# Half_Slave.net
KiCad netlist of a schematic drawn in Altium Designer
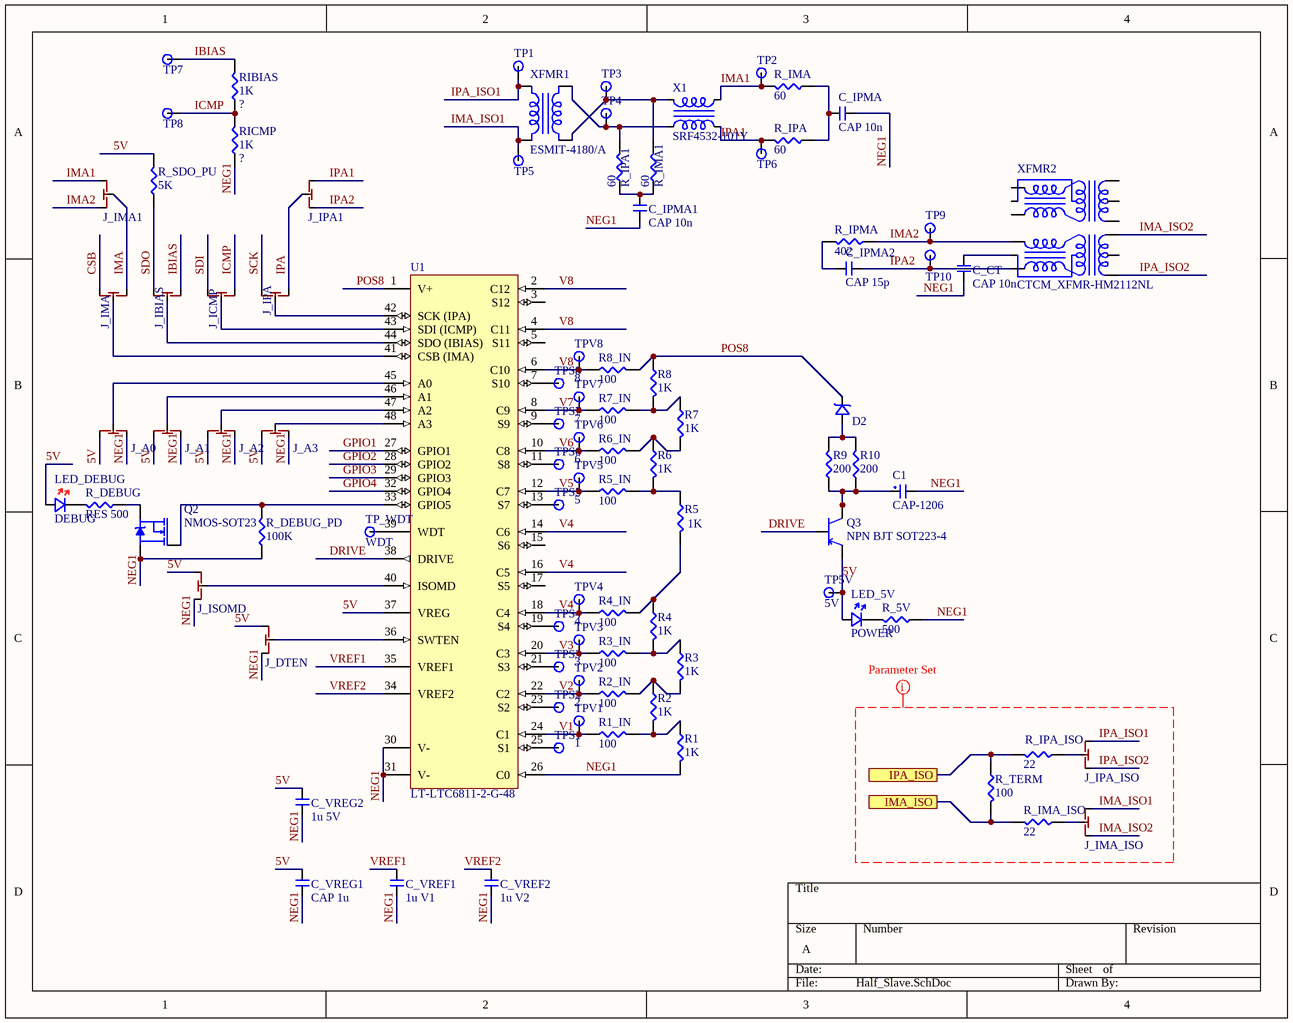
[diagram p0: Half_Slave.SchDoc]

(export (version "E")
  (design (tool "Eeschema 10.0.6"))
  (components
    (comp (ref "C1")
      (value "CAP-1206")
      (footprint "CAPCP3216X16N")
      (libsource (lib "LTC6811") (part "CAP-1206"))
    )
    (comp (ref "C_CT")
      (value "CAP 10n")
      (footprint "CAP-0603")
      (description "CAP-0603")
      (libsource (lib "ife18_TS_BMS_LTC6813_v2_Library") (part "CAP-0603"))
    )
    (comp (ref "C_IPMA")
      (value "CAP 10n")
      (footprint "CAP-0603")
      (description "CAP-0603")
      (libsource (lib "ife18_TS_BMS_LTC6813_v2_Library") (part "CAP-0603"))
    )
    (comp (ref "C_IPMA1")
      (value "CAP 10n")
      (footprint "CAP-0603")
      (description "CAP-0603")
      (libsource (lib "ife18_TS_BMS_LTC6813_v2_Library") (part "CAP-0603"))
    )
    (comp (ref "C_IPMA2")
      (value "CAP 15p")
      (footprint "CAP-0603")
      (description "CAP-0603")
      (libsource (lib "ife18_TS_BMS_LTC6813_v2_Library") (part "CAP-0603"))
    )
    (comp (ref "C_VREF1")
      (value "1u V1")
      (footprint "CAP-0603")
      (description "CAP-0603")
      (libsource (lib "altium-import") (part "root_1_CAP-0603_"))
    )
    (comp (ref "C_VREF2")
      (value "1u V2")
      (footprint "CAP-0603")
      (description "CAP-0603")
      (libsource (lib "altium-import") (part "root_1_CAP-0603_"))
    )
    (comp (ref "C_VREG1")
      (value "CAP 1u")
      (footprint "CAP-0603")
      (description "CAP-0603")
      (libsource (lib "altium-import") (part "root_1_CAP-0603_"))
    )
    (comp (ref "C_VREG2")
      (value "1u 5V")
      (footprint "CAP-0603")
      (description "CAP-0603")
      (libsource (lib "altium-import") (part "root_1_CAP-0603_"))
    )
    (comp (ref "D2") (value "?") (footprint "SMB") (libsource (lib "ife19_Elec_Library") (part "DIODE-SMB")))
    (comp (ref "J_A0")
      (value "DPDT Solder Jumper")
      (footprint "DPDT Solder")
      (libsource (lib "LTC6811") (part "DPDT Solder"))
    )
    (comp (ref "J_A1")
      (value "DPDT Solder Jumper")
      (footprint "DPDT Solder")
      (libsource (lib "LTC6811") (part "DPDT Solder"))
    )
    (comp (ref "J_A2")
      (value "DPDT Solder Jumper")
      (footprint "DPDT Solder")
      (libsource (lib "LTC6811") (part "DPDT Solder"))
    )
    (comp (ref "J_A3")
      (value "DPDT Solder Jumper")
      (footprint "DPDT Solder")
      (libsource (lib "LTC6811") (part "DPDT Solder"))
    )
    (comp (ref "J_DTEN")
      (value "DPDT Solder Jumper")
      (footprint "DPDT Solder")
      (libsource (lib "LTC6811") (part "DPDT Solder"))
    )
    (comp (ref "J_IBIAS")
      (value "DPDT Solder Jumper")
      (footprint "DPDT Solder")
      (libsource (lib "LTC6811") (part "DPDT Solder"))
    )
    (comp (ref "J_ICMP")
      (value "DPDT Solder Jumper")
      (footprint "DPDT Solder")
      (libsource (lib "LTC6811") (part "DPDT Solder"))
    )
    (comp (ref "J_IMA")
      (value "DPDT Solder Jumper")
      (footprint "DPDT Solder")
      (libsource (lib "LTC6811") (part "DPDT Solder"))
    )
    (comp (ref "J_IMA1")
      (value "DPDT Solder Jumper")
      (footprint "DPDT Solder")
      (libsource (lib "LTC6811") (part "DPDT Solder"))
    )
    (comp (ref "J_IMA_ISO")
      (value "DPDT Solder Jumper")
      (footprint "DPDT Solder")
      (libsource (lib "LTC6811") (part "DPDT Solder"))
    )
    (comp (ref "J_IPA")
      (value "DPDT Solder Jumper")
      (footprint "DPDT Solder")
      (libsource (lib "LTC6811") (part "DPDT Solder"))
    )
    (comp (ref "J_IPA1")
      (value "DPDT Solder Jumper")
      (footprint "DPDT Solder")
      (libsource (lib "LTC6811") (part "DPDT Solder"))
    )
    (comp (ref "J_IPA_ISO")
      (value "DPDT Solder Jumper")
      (footprint "DPDT Solder")
      (libsource (lib "LTC6811") (part "DPDT Solder"))
    )
    (comp (ref "J_ISOMD")
      (value "DPDT Solder Jumper")
      (footprint "DPDT Solder")
      (libsource (lib "LTC6811") (part "DPDT Solder"))
    )
    (comp (ref "LED_5V")
      (value "POWER")
      (footprint "LEDBLUE-0603")
      (libsource (lib "ife19_Elec_Library") (part "LEDBLUE-0603"))
    )
    (comp (ref "LED_DEBUG")
      (value "DEBUG")
      (footprint "LEDRED-0603")
      (libsource (lib "ife19_Elec_Library") (part "LEDRED-0603"))
    )
    (comp (ref "Q2")
      (value "NMOS-SOT23")
      (footprint "SOT23")
      (libsource (lib "ife19_Elec_Library") (part "NMOS-SOT23"))
    )
    (comp (ref "Q3")
      (value "NPN BJT SOT223-4")
      (footprint "SOT223")
      (description "BCP54,115")
      (libsource (lib "ife19_Elec_Library") (part "NPN_SOT223-4"))
    )
    (comp (ref "R1")
      (value "1K")
      (footprint "RES-0603")
      (libsource (lib "ife18_TS_BMS_LTC6813_v2_Library") (part "RES-0603"))
    )
    (comp (ref "R1_IN")
      (value "100")
      (footprint "RES-0603")
      (libsource (lib "ife18_TS_BMS_LTC6813_v2_Library") (part "RES-0603"))
    )
    (comp (ref "R2")
      (value "1K")
      (footprint "RES-0603")
      (libsource (lib "ife18_TS_BMS_LTC6813_v2_Library") (part "RES-0603"))
    )
    (comp (ref "R2_IN")
      (value "100")
      (footprint "RES-0603")
      (libsource (lib "ife18_TS_BMS_LTC6813_v2_Library") (part "RES-0603"))
    )
    (comp (ref "R3")
      (value "1K")
      (footprint "RES-0603")
      (libsource (lib "ife18_TS_BMS_LTC6813_v2_Library") (part "RES-0603"))
    )
    (comp (ref "R3_IN")
      (value "100")
      (footprint "RES-0603")
      (libsource (lib "ife18_TS_BMS_LTC6813_v2_Library") (part "RES-0603"))
    )
    (comp (ref "R4")
      (value "1K")
      (footprint "RES-0603")
      (libsource (lib "ife18_TS_BMS_LTC6813_v2_Library") (part "RES-0603"))
    )
    (comp (ref "R4_IN")
      (value "100")
      (footprint "RES-0603")
      (libsource (lib "ife18_TS_BMS_LTC6813_v2_Library") (part "RES-0603"))
    )
    (comp (ref "R5")
      (value "1K")
      (footprint "RES-0603")
      (libsource (lib "ife18_TS_BMS_LTC6813_v2_Library") (part "RES-0603"))
    )
    (comp (ref "R5_IN")
      (value "100")
      (footprint "RES-0603")
      (libsource (lib "ife18_TS_BMS_LTC6813_v2_Library") (part "RES-0603"))
    )
    (comp (ref "R6")
      (value "1K")
      (footprint "RES-0603")
      (libsource (lib "ife18_TS_BMS_LTC6813_v2_Library") (part "RES-0603"))
    )
    (comp (ref "R6_IN")
      (value "100")
      (footprint "RES-0603")
      (libsource (lib "ife18_TS_BMS_LTC6813_v2_Library") (part "RES-0603"))
    )
    (comp (ref "R7")
      (value "1K")
      (footprint "RES-0603")
      (libsource (lib "ife18_TS_BMS_LTC6813_v2_Library") (part "RES-0603"))
    )
    (comp (ref "R7_IN")
      (value "100")
      (footprint "RES-0603")
      (libsource (lib "ife18_TS_BMS_LTC6813_v2_Library") (part "RES-0603"))
    )
    (comp (ref "R8")
      (value "1K")
      (footprint "RES-0603")
      (libsource (lib "ife18_TS_BMS_LTC6813_v2_Library") (part "RES-0603"))
    )
    (comp (ref "R8_IN")
      (value "100")
      (footprint "RES-0603")
      (libsource (lib "ife18_TS_BMS_LTC6813_v2_Library") (part "RES-0603"))
    )
    (comp (ref "R9")
      (value "200")
      (footprint "RES-0603")
      (libsource (lib "ife18_TS_BMS_LTC6813_v2_Library") (part "RES-0603"))
    )
    (comp (ref "R10")
      (value "200")
      (footprint "RES-0603")
      (libsource (lib "ife18_TS_BMS_LTC6813_v2_Library") (part "RES-0603"))
    )
    (comp (ref "RIBIAS")
      (value "1K")
      (footprint "RES-0603")
      (description "RES SMD 0603")
      (fields (field (name "PART") "RES_0603") (field (name "ALTIUM_VALUE") "?"))
      (libsource (lib "IFE") (part "RES"))
    )
    (comp (ref "RICMP")
      (value "1K")
      (footprint "RES-0603")
      (description "RES SMD 0603")
      (fields (field (name "PART") "RES_0603") (field (name "ALTIUM_VALUE") "?"))
      (libsource (lib "IFE") (part "RES"))
    )
    (comp (ref "R_5V")
      (value "500")
      (footprint "RES-0603")
      (libsource (lib "altium-import") (part "root_2_RES-0603_"))
    )
    (comp (ref "R_DEBUG")
      (value "RES 500")
      (footprint "RES-0603")
      (libsource (lib "altium-import") (part "root_2_RES-0603_"))
    )
    (comp (ref "R_DEBUG_PD")
      (value "100K")
      (footprint "RES-0603")
      (libsource (lib "ife18_TS_BMS_LTC6813_v2_Library") (part "RES-0603"))
    )
    (comp (ref "R_IMA")
      (value "60")
      (footprint "RES-0603")
      (libsource (lib "ife18_TS_BMS_LTC6813_v2_Library") (part "RES-0603"))
    )
    (comp (ref "R_IMA1")
      (value "60")
      (footprint "RES-0603")
      (libsource (lib "ife18_TS_BMS_LTC6813_v2_Library") (part "RES-0603"))
    )
    (comp (ref "R_IMA_ISO")
      (value "22")
      (footprint "RES-0603")
      (libsource (lib "ife18_TS_BMS_LTC6813_v2_Library") (part "RES-0603"))
    )
    (comp (ref "R_IPA")
      (value "60")
      (footprint "RES-0603")
      (libsource (lib "ife18_TS_BMS_LTC6813_v2_Library") (part "RES-0603"))
    )
    (comp (ref "R_IPA1")
      (value "60")
      (footprint "RES-0603")
      (libsource (lib "ife18_TS_BMS_LTC6813_v2_Library") (part "RES-0603"))
    )
    (comp (ref "R_IPA_ISO")
      (value "22")
      (footprint "RES-0603")
      (libsource (lib "ife18_TS_BMS_LTC6813_v2_Library") (part "RES-0603"))
    )
    (comp (ref "R_IPMA")
      (value "402")
      (footprint "RES-0603")
      (libsource (lib "ife18_TS_BMS_LTC6813_v2_Library") (part "RES-0603"))
    )
    (comp (ref "R_SDO_PU")
      (value "5K")
      (footprint "RES-0603")
      (libsource (lib "ife18_TS_BMS_LTC6813_v2_Library") (part "RES-0603"))
    )
    (comp (ref "R_TERM")
      (value "100")
      (footprint "RES-0603")
      (libsource (lib "ife18_TS_BMS_LTC6813_v2_Library") (part "RES-0603"))
    )
    (comp (ref "TP1")
      (value "IP_ISO")
      (footprint "Testpoint")
      (libsource (lib "ife19_Elec_Library") (part "Testpoint"))
    )
    (comp (ref "TP2")
      (value "IMA")
      (footprint "Testpoint")
      (libsource (lib "ife19_Elec_Library") (part "Testpoint"))
    )
    (comp (ref "TP3")
      (value "IM_F")
      (footprint "Testpoint")
      (libsource (lib "ife19_Elec_Library") (part "Testpoint"))
    )
    (comp (ref "TP4")
      (value "IP_F")
      (footprint "Testpoint")
      (libsource (lib "ife19_Elec_Library") (part "Testpoint"))
    )
    (comp (ref "TP5")
      (value "IM_ISO")
      (footprint "Testpoint")
      (libsource (lib "ife19_Elec_Library") (part "Testpoint"))
    )
    (comp (ref "TP5V")
      (value "5V")
      (footprint "Testpoint")
      (libsource (lib "ife19_Elec_Library") (part "Testpoint"))
    )
    (comp (ref "TP6")
      (value "IPA")
      (footprint "Testpoint")
      (libsource (lib "ife19_Elec_Library") (part "Testpoint"))
    )
    (comp (ref "TP7")
      (value "IBIAS")
      (footprint "Testpoint")
      (libsource (lib "ife19_Elec_Library") (part "Testpoint"))
    )
    (comp (ref "TP8")
      (value "ICMP")
      (footprint "Testpoint")
      (libsource (lib "ife19_Elec_Library") (part "Testpoint"))
    )
    (comp (ref "TP9")
      (value "IMA")
      (footprint "Testpoint")
      (libsource (lib "ife19_Elec_Library") (part "Testpoint"))
    )
    (comp (ref "TP10")
      (value "IPA")
      (footprint "Testpoint")
      (libsource (lib "ife19_Elec_Library") (part "Testpoint"))
    )
    (comp (ref "TPS1")
      (value "~")
      (footprint "Testpoint")
      (libsource (lib "ife19_Elec_Library") (part "Testpoint"))
    )
    (comp (ref "TPS2")
      (value "~")
      (footprint "Testpoint")
      (libsource (lib "ife19_Elec_Library") (part "Testpoint"))
    )
    (comp (ref "TPS3")
      (value "~")
      (footprint "Testpoint")
      (libsource (lib "ife19_Elec_Library") (part "Testpoint"))
    )
    (comp (ref "TPS4")
      (value "~")
      (footprint "Testpoint")
      (libsource (lib "ife19_Elec_Library") (part "Testpoint"))
    )
    (comp (ref "TPS5")
      (value "~")
      (footprint "Testpoint")
      (libsource (lib "ife19_Elec_Library") (part "Testpoint"))
    )
    (comp (ref "TPS6")
      (value "~")
      (footprint "Testpoint")
      (libsource (lib "ife19_Elec_Library") (part "Testpoint"))
    )
    (comp (ref "TPS7")
      (value "~")
      (footprint "Testpoint")
      (libsource (lib "ife19_Elec_Library") (part "Testpoint"))
    )
    (comp (ref "TPS8")
      (value "~")
      (footprint "Testpoint")
      (libsource (lib "ife19_Elec_Library") (part "Testpoint"))
    )
    (comp (ref "TPV1")
      (value "1")
      (footprint "Testpoint")
      (libsource (lib "ife19_Elec_Library") (part "Testpoint"))
    )
    (comp (ref "TPV2")
      (value "2")
      (footprint "Testpoint")
      (libsource (lib "ife19_Elec_Library") (part "Testpoint"))
    )
    (comp (ref "TPV3")
      (value "3")
      (footprint "Testpoint")
      (libsource (lib "ife19_Elec_Library") (part "Testpoint"))
    )
    (comp (ref "TPV4")
      (value "4")
      (footprint "Testpoint")
      (libsource (lib "ife19_Elec_Library") (part "Testpoint"))
    )
    (comp (ref "TPV5")
      (value "5")
      (footprint "Testpoint")
      (libsource (lib "ife19_Elec_Library") (part "Testpoint"))
    )
    (comp (ref "TPV6")
      (value "6")
      (footprint "Testpoint")
      (libsource (lib "ife19_Elec_Library") (part "Testpoint"))
    )
    (comp (ref "TPV7")
      (value "7")
      (footprint "Testpoint")
      (libsource (lib "ife19_Elec_Library") (part "Testpoint"))
    )
    (comp (ref "TPV8")
      (value "8")
      (footprint "Testpoint")
      (libsource (lib "ife19_Elec_Library") (part "Testpoint"))
    )
    (comp (ref "TP_WDT")
      (value "WDT")
      (footprint "Testpoint")
      (libsource (lib "ife19_Elec_Library") (part "Testpoint"))
    )
    (comp (ref "U1")
      (value "LT-LTC6811-2-G-48")
      (footprint "SSOP-48N")
      (libsource (lib "LTC6811") (part "LT-LTC6811-2-G-48"))
    )
    (comp (ref "X1")
      (value "SRF4532-101Y")
      (footprint "SRF4532")
      (libsource (lib "ife19_Elec_Library") (part "CMC_SRF4532"))
    )
    (comp (ref "XFMR1")
      (value "ESMIT-4180/A")
      (footprint "ISOXFMR_ESMIT4180")
      (libsource (lib "ife19_Elec_Library") (part "ISOXFMR_ESMIT4180"))
    )
    (comp (ref "XFMR2")
      (value "CTCM_XFMR-HM2112NL")
      (footprint "HM2112NL")
      (libsource (lib "ife19_Elec_Library") (part "CTCM_XFMR-HM2112NL"))
    )
  )
  (nets
    (net (code "1") (name "/5V") (class "Default")
      (node (ref "C_VREG1") (pin "2") (pinfunction "2_2") (pintype "passive"))
      (node (ref "C_VREG2") (pin "2") (pinfunction "2_2") (pintype "passive"))
      (node (ref "J_A0") (pin "2") (pintype "passive"))
      (node (ref "J_A1") (pin "2") (pintype "passive"))
      (node (ref "J_A2") (pin "2") (pintype "passive"))
      (node (ref "J_A3") (pin "2") (pintype "passive"))
      (node (ref "J_DTEN") (pin "2") (pintype "passive"))
      (node (ref "J_ISOMD") (pin "2") (pintype "passive"))
      (node (ref "LED_5V") (pin "A") (pinfunction "A_A") (pintype "passive"))
      (node (ref "LED_DEBUG") (pin "A") (pinfunction "A_A") (pintype "passive"))
      (node (ref "Q3") (pin "3") (pinfunction "E_3") (pintype "passive"))
      (node (ref "R_SDO_PU") (pin "2") (pinfunction "2_2") (pintype "passive"))
      (node (ref "TP5V") (pin "1") (pinfunction "1_1") (pintype "passive"))
      (node (ref "U1") (pin "37") (pinfunction "VREG_37") (pintype "power_in"))
    )
    (net (code "2") (name "/CSB") (class "Default") (node (ref "J_IMA") (pin "1") (pintype "passive")))
    (net (code "3") (name "/DRIVE") (class "Default")
      (node (ref "Q3") (pin "1") (pinfunction "B_1") (pintype "passive"))
      (node (ref "U1") (pin "38") (pinfunction "DRIVE_38") (pintype "output"))
    )
    (net (code "4") (name "/GPIO1") (class "Default")
      (node (ref "U1") (pin "27") (pinfunction "GPIO1_27") (pintype "bidirectional"))
    )
    (net (code "5") (name "/GPIO2") (class "Default")
      (node (ref "U1") (pin "28") (pinfunction "GPIO2_28") (pintype "bidirectional"))
    )
    (net (code "6") (name "/GPIO3") (class "Default")
      (node (ref "U1") (pin "29") (pinfunction "GPIO3_29") (pintype "bidirectional"))
    )
    (net (code "7") (name "/GPIO4") (class "Default")
      (node (ref "U1") (pin "32") (pinfunction "GPIO4_32") (pintype "bidirectional"))
    )
    (net (code "8") (name "/IBIAS") (class "Default")
      (node (ref "J_IBIAS") (pin "2") (pintype "passive"))
      (node (ref "RIBIAS") (pin "2") (pinfunction "2_2") (pintype "passive"))
      (node (ref "TP7") (pin "1") (pinfunction "1_1") (pintype "passive"))
    )
    (net (code "9") (name "/ICMP") (class "Default")
      (node (ref "J_ICMP") (pin "2") (pintype "passive"))
      (node (ref "RIBIAS") (pin "1") (pinfunction "1_1") (pintype "passive"))
      (node (ref "RICMP") (pin "2") (pinfunction "2_2") (pintype "passive"))
      (node (ref "TP8") (pin "1") (pinfunction "1_1") (pintype "passive"))
    )
    (net (code "10") (name "/IMA") (class "Default")
      (node (ref "J_IMA") (pin "2") (pintype "passive"))
      (node (ref "J_IMA1") (pin "3") (pintype "passive"))
    )
    (net (code "11") (name "/IMA1") (class "Default")
      (node (ref "J_IMA1") (pin "2") (pintype "passive"))
      (node (ref "R_IMA") (pin "2") (pinfunction "2_2") (pintype "passive"))
      (node (ref "TP2") (pin "1") (pinfunction "1_1") (pintype "passive"))
      (node (ref "X1") (pin "1") (pinfunction "1_1") (pintype "passive"))
    )
    (net (code "12") (name "/IMA2") (class "Default")
      (node (ref "J_IMA1") (pin "1") (pintype "passive"))
      (node (ref "R_IPMA") (pin "1") (pinfunction "1_1") (pintype "passive"))
      (node (ref "TP9") (pin "1") (pinfunction "1_1") (pintype "passive"))
      (node (ref "XFMR2") (pin "9") (pinfunction "9_9") (pintype "passive"))
    )
    (net (code "13") (name "/IMA_ISO") (class "Default")
      (node (ref "R_IMA_ISO") (pin "2") (pinfunction "2_2") (pintype "passive"))
      (node (ref "R_TERM") (pin "2") (pinfunction "2_2") (pintype "passive"))
    )
    (net (code "14") (name "/IMA_ISO1") (class "Default")
      (node (ref "J_IMA_ISO") (pin "2") (pintype "passive"))
      (node (ref "TP5") (pin "1") (pinfunction "1_1") (pintype "passive"))
      (node (ref "XFMR1") (pin "1") (pinfunction "1_1") (pintype "passive"))
    )
    (net (code "15") (name "/IMA_ISO2") (class "Default")
      (node (ref "J_IMA_ISO") (pin "1") (pintype "passive"))
      (node (ref "XFMR2") (pin "4") (pinfunction "4_4") (pintype "passive"))
    )
    (net (code "16") (name "/IPA") (class "Default")
      (node (ref "J_IPA") (pin "2") (pintype "passive"))
      (node (ref "J_IPA1") (pin "3") (pintype "passive"))
    )
    (net (code "17") (name "/IPA1") (class "Default")
      (node (ref "J_IPA1") (pin "2") (pintype "passive"))
      (node (ref "R_IPA") (pin "2") (pinfunction "2_2") (pintype "passive"))
      (node (ref "TP6") (pin "1") (pinfunction "1_1") (pintype "passive"))
      (node (ref "X1") (pin "4") (pinfunction "4_4") (pintype "passive"))
    )
    (net (code "18") (name "/IPA2") (class "Default")
      (node (ref "C_IPMA2") (pin "1") (pinfunction "1_1") (pintype "passive"))
      (node (ref "J_IPA1") (pin "1") (pintype "passive"))
      (node (ref "TP10") (pin "1") (pinfunction "1_1") (pintype "passive"))
      (node (ref "XFMR2") (pin "7") (pinfunction "7_7") (pintype "passive"))
    )
    (net (code "19") (name "/IPA_ISO") (class "Default")
      (node (ref "R_IPA_ISO") (pin "2") (pinfunction "2_2") (pintype "passive"))
      (node (ref "R_TERM") (pin "1") (pinfunction "1_1") (pintype "passive"))
    )
    (net (code "20") (name "/IPA_ISO1") (class "Default")
      (node (ref "J_IPA_ISO") (pin "2") (pintype "passive"))
      (node (ref "TP1") (pin "1") (pinfunction "1_1") (pintype "passive"))
      (node (ref "XFMR1") (pin "2") (pinfunction "2_2") (pintype "passive"))
    )
    (net (code "21") (name "/IPA_ISO2") (class "Default")
      (node (ref "J_IPA_ISO") (pin "1") (pintype "passive"))
      (node (ref "XFMR2") (pin "6") (pinfunction "6_6") (pintype "passive"))
    )
    (net (code "22") (name "/NEG1") (class "Default")
      (node (ref "C1") (pin "2") (pinfunction "2_2") (pintype "passive"))
      (node (ref "C_CT") (pin "2") (pinfunction "2_2") (pintype "passive"))
      (node (ref "C_IPMA") (pin "1") (pinfunction "1_1") (pintype "passive"))
      (node (ref "C_IPMA1") (pin "1") (pinfunction "1_1") (pintype "passive"))
      (node (ref "C_VREF1") (pin "1") (pinfunction "1_1") (pintype "passive"))
      (node (ref "C_VREF2") (pin "1") (pinfunction "1_1") (pintype "passive"))
      (node (ref "C_VREG1") (pin "1") (pinfunction "1_1") (pintype "passive"))
      (node (ref "C_VREG2") (pin "1") (pinfunction "1_1") (pintype "passive"))
      (node (ref "J_A0") (pin "1") (pintype "passive"))
      (node (ref "J_A1") (pin "1") (pintype "passive"))
      (node (ref "J_A2") (pin "1") (pintype "passive"))
      (node (ref "J_A3") (pin "1") (pintype "passive"))
      (node (ref "J_DTEN") (pin "1") (pintype "passive"))
      (node (ref "J_ISOMD") (pin "1") (pintype "passive"))
      (node (ref "Q2") (pin "2") (pinfunction "S_2") (pintype "passive"))
      (node (ref "R1") (pin "2") (pinfunction "2_2") (pintype "passive"))
      (node (ref "RICMP") (pin "1") (pinfunction "1_1") (pintype "passive"))
      (node (ref "R_5V") (pin "1") (pinfunction "1_1") (pintype "passive"))
      (node (ref "R_DEBUG_PD") (pin "1") (pinfunction "1_1") (pintype "passive"))
      (node (ref "U1") (pin "26") (pinfunction "C0_26") (pintype "input"))
      (node (ref "U1") (pin "30") (pinfunction "V-_30") (pintype "power_in"))
      (node (ref "U1") (pin "31") (pinfunction "V-_31") (pintype "power_in"))
    )
    (net (code "23") (name "/POS8") (class "Default")
      (node (ref "D2") (pin "K") (pinfunction "K_K") (pintype "passive"))
      (node (ref "R8") (pin "1") (pinfunction "1_1") (pintype "passive"))
      (node (ref "R8_IN") (pin "2") (pinfunction "2_2") (pintype "passive"))
      (node (ref "U1") (pin "1") (pinfunction "V+_1") (pintype "power_in"))
    )
    (net (code "24") (name "/SCK") (class "Default") (node (ref "J_IPA") (pin "1") (pintype "passive")))
    (net (code "25") (name "/SDI") (class "Default") (node (ref "J_ICMP") (pin "1") (pintype "passive")))
    (net (code "26") (name "/SDO") (class "Default")
      (node (ref "J_IBIAS") (pin "1") (pintype "passive"))
      (node (ref "R_SDO_PU") (pin "1") (pinfunction "1_1") (pintype "passive"))
    )
    (net (code "27") (name "/V1") (class "Default")
      (node (ref "R1_IN") (pin "1") (pinfunction "1_1") (pintype "passive"))
      (node (ref "TPV1") (pin "1") (pinfunction "1_1") (pintype "passive"))
      (node (ref "U1") (pin "24") (pinfunction "C1_24") (pintype "input"))
    )
    (net (code "28") (name "/V2") (class "Default")
      (node (ref "R2_IN") (pin "1") (pinfunction "1_1") (pintype "passive"))
      (node (ref "TPV2") (pin "1") (pinfunction "1_1") (pintype "passive"))
      (node (ref "U1") (pin "22") (pinfunction "C2_22") (pintype "input"))
    )
    (net (code "29") (name "/V3") (class "Default")
      (node (ref "R3_IN") (pin "1") (pinfunction "1_1") (pintype "passive"))
      (node (ref "TPV3") (pin "1") (pinfunction "1_1") (pintype "passive"))
      (node (ref "U1") (pin "20") (pinfunction "C3_20") (pintype "input"))
    )
    (net (code "30") (name "/V4") (class "Default")
      (node (ref "R4_IN") (pin "1") (pinfunction "1_1") (pintype "passive"))
      (node (ref "TPV4") (pin "1") (pinfunction "1_1") (pintype "passive"))
      (node (ref "U1") (pin "14") (pinfunction "C6_14") (pintype "input"))
      (node (ref "U1") (pin "16") (pinfunction "C5_16") (pintype "input"))
      (node (ref "U1") (pin "18") (pinfunction "C4_18") (pintype "input"))
    )
    (net (code "31") (name "/V5") (class "Default")
      (node (ref "R5_IN") (pin "1") (pinfunction "1_1") (pintype "passive"))
      (node (ref "TPV5") (pin "1") (pinfunction "1_1") (pintype "passive"))
      (node (ref "U1") (pin "12") (pinfunction "C7_12") (pintype "input"))
    )
    (net (code "32") (name "/V6") (class "Default")
      (node (ref "R6_IN") (pin "1") (pinfunction "1_1") (pintype "passive"))
      (node (ref "TPV6") (pin "1") (pinfunction "1_1") (pintype "passive"))
      (node (ref "U1") (pin "10") (pinfunction "C8_10") (pintype "input"))
    )
    (net (code "33") (name "/V7") (class "Default")
      (node (ref "R7_IN") (pin "1") (pinfunction "1_1") (pintype "passive"))
      (node (ref "TPV7") (pin "1") (pinfunction "1_1") (pintype "passive"))
      (node (ref "U1") (pin "8") (pinfunction "C9_8") (pintype "input"))
    )
    (net (code "34") (name "/V8") (class "Default")
      (node (ref "R8_IN") (pin "1") (pinfunction "1_1") (pintype "passive"))
      (node (ref "TPV8") (pin "1") (pinfunction "1_1") (pintype "passive"))
      (node (ref "U1") (pin "2") (pinfunction "C12_2") (pintype "input"))
      (node (ref "U1") (pin "4") (pinfunction "C11_4") (pintype "input"))
      (node (ref "U1") (pin "6") (pinfunction "C10_6") (pintype "input"))
    )
    (net (code "35") (name "/VREF1") (class "Default")
      (node (ref "C_VREF1") (pin "2") (pinfunction "2_2") (pintype "passive"))
      (node (ref "U1") (pin "35") (pinfunction "VREF1_35") (pintype "passive"))
    )
    (net (code "36") (name "/VREF2") (class "Default")
      (node (ref "C_VREF2") (pin "2") (pinfunction "2_2") (pintype "passive"))
      (node (ref "U1") (pin "34") (pinfunction "VREF2_34") (pintype "passive"))
    )
    (net (code "37") (name "Net-(C1-Pad1)") (class "Default")
      (node (ref "C1") (pin "1") (pinfunction "1_1") (pintype "passive"))
      (node (ref "Q3") (pin "2") (pinfunction "C_2") (pintype "passive"))
      (node (ref "Q3") (pin "4") (pinfunction "C_4") (pintype "passive"))
      (node (ref "R10") (pin "1") (pinfunction "1_1") (pintype "passive"))
      (node (ref "R9") (pin "1") (pinfunction "1_1") (pintype "passive"))
    )
    (net (code "38") (name "Net-(C_CT-Pad1)") (class "Default")
      (node (ref "C_CT") (pin "1") (pinfunction "1_1") (pintype "passive"))
      (node (ref "XFMR2") (pin "8") (pinfunction "8_8") (pintype "passive"))
    )
    (net (code "39") (name "Net-(C_IPMA-Pad2)") (class "Default")
      (node (ref "C_IPMA") (pin "2") (pinfunction "2_2") (pintype "passive"))
      (node (ref "R_IMA") (pin "1") (pinfunction "1_1") (pintype "passive"))
      (node (ref "R_IPA") (pin "1") (pinfunction "1_1") (pintype "passive"))
    )
    (net (code "40") (name "Net-(C_IPMA1-Pad2)") (class "Default")
      (node (ref "C_IPMA1") (pin "2") (pinfunction "2_2") (pintype "passive"))
      (node (ref "R_IMA1") (pin "1") (pinfunction "1_1") (pintype "passive"))
      (node (ref "R_IPA1") (pin "1") (pinfunction "1_1") (pintype "passive"))
    )
    (net (code "41") (name "Net-(C_IPMA2-Pad2)") (class "Default")
      (node (ref "C_IPMA2") (pin "2") (pinfunction "2_2") (pintype "passive"))
      (node (ref "R_IPMA") (pin "2") (pinfunction "2_2") (pintype "passive"))
    )
    (net (code "42") (name "Net-(D2-PadA)") (class "Default")
      (node (ref "D2") (pin "A") (pinfunction "A_A") (pintype "passive"))
      (node (ref "R10") (pin "2") (pinfunction "2_2") (pintype "passive"))
      (node (ref "R9") (pin "2") (pinfunction "2_2") (pintype "passive"))
    )
    (net (code "43") (name "Net-(J_IMA_ISO-Pad3)") (class "Default")
      (node (ref "J_IMA_ISO") (pin "3") (pintype "passive"))
      (node (ref "R_IMA_ISO") (pin "1") (pinfunction "1_1") (pintype "passive"))
    )
    (net (code "44") (name "Net-(J_IPA_ISO-Pad3)") (class "Default")
      (node (ref "J_IPA_ISO") (pin "3") (pintype "passive"))
      (node (ref "R_IPA_ISO") (pin "1") (pinfunction "1_1") (pintype "passive"))
    )
    (net (code "45") (name "Net-(LED_5V-PadK)") (class "Default")
      (node (ref "LED_5V") (pin "K") (pinfunction "K_K") (pintype "passive"))
      (node (ref "R_5V") (pin "2") (pinfunction "2_2") (pintype "passive"))
    )
    (net (code "46") (name "Net-(LED_DEBUG-PadK)") (class "Default")
      (node (ref "LED_DEBUG") (pin "K") (pinfunction "K_K") (pintype "passive"))
      (node (ref "R_DEBUG") (pin "2") (pinfunction "2_2") (pintype "passive"))
    )
    (net (code "47") (name "Net-(Q2-D)") (class "Default")
      (node (ref "Q2") (pin "3") (pinfunction "D_3") (pintype "passive"))
      (node (ref "R_DEBUG") (pin "1") (pinfunction "1_1") (pintype "passive"))
    )
    (net (code "48") (name "Net-(Q2-G)") (class "Default")
      (node (ref "Q2") (pin "1") (pinfunction "G_1") (pintype "passive"))
      (node (ref "R_DEBUG_PD") (pin "2") (pinfunction "2_2") (pintype "passive"))
      (node (ref "U1") (pin "33") (pinfunction "GPIO5_33") (pintype "bidirectional"))
    )
    (net (code "49") (name "Net-(R1-Pad1)") (class "Default")
      (node (ref "R1") (pin "1") (pinfunction "1_1") (pintype "passive"))
      (node (ref "R1_IN") (pin "2") (pinfunction "2_2") (pintype "passive"))
      (node (ref "R2") (pin "2") (pinfunction "2_2") (pintype "passive"))
    )
    (net (code "50") (name "Net-(R2-Pad1)") (class "Default")
      (node (ref "R2") (pin "1") (pinfunction "1_1") (pintype "passive"))
      (node (ref "R2_IN") (pin "2") (pinfunction "2_2") (pintype "passive"))
      (node (ref "R3") (pin "2") (pinfunction "2_2") (pintype "passive"))
    )
    (net (code "51") (name "Net-(R3-Pad1)") (class "Default")
      (node (ref "R3") (pin "1") (pinfunction "1_1") (pintype "passive"))
      (node (ref "R3_IN") (pin "2") (pinfunction "2_2") (pintype "passive"))
      (node (ref "R4") (pin "2") (pinfunction "2_2") (pintype "passive"))
    )
    (net (code "52") (name "Net-(R4-Pad1)") (class "Default")
      (node (ref "R4") (pin "1") (pinfunction "1_1") (pintype "passive"))
      (node (ref "R4_IN") (pin "2") (pinfunction "2_2") (pintype "passive"))
      (node (ref "R5") (pin "2") (pinfunction "2_2") (pintype "passive"))
    )
    (net (code "53") (name "Net-(R5-Pad1)") (class "Default")
      (node (ref "R5") (pin "1") (pinfunction "1_1") (pintype "passive"))
      (node (ref "R5_IN") (pin "2") (pinfunction "2_2") (pintype "passive"))
      (node (ref "R6") (pin "2") (pinfunction "2_2") (pintype "passive"))
    )
    (net (code "54") (name "Net-(R6-Pad1)") (class "Default")
      (node (ref "R6") (pin "1") (pinfunction "1_1") (pintype "passive"))
      (node (ref "R6_IN") (pin "2") (pinfunction "2_2") (pintype "passive"))
      (node (ref "R7") (pin "2") (pinfunction "2_2") (pintype "passive"))
    )
    (net (code "55") (name "Net-(R7-Pad1)") (class "Default")
      (node (ref "R7") (pin "1") (pinfunction "1_1") (pintype "passive"))
      (node (ref "R7_IN") (pin "2") (pinfunction "2_2") (pintype "passive"))
      (node (ref "R8") (pin "2") (pinfunction "2_2") (pintype "passive"))
    )
    (net (code "56") (name "Net-(R_IMA1-Pad2)") (class "Default")
      (node (ref "R_IMA1") (pin "2") (pinfunction "2_2") (pintype "passive"))
      (node (ref "TP3") (pin "1") (pinfunction "1_1") (pintype "passive"))
      (node (ref "X1") (pin "2") (pinfunction "2_2") (pintype "passive"))
      (node (ref "XFMR1") (pin "4") (pinfunction "4_4") (pintype "passive"))
    )
    (net (code "57") (name "Net-(R_IPA1-Pad2)") (class "Default")
      (node (ref "R_IPA1") (pin "2") (pinfunction "2_2") (pintype "passive"))
      (node (ref "TP4") (pin "1") (pinfunction "1_1") (pintype "passive"))
      (node (ref "X1") (pin "3") (pinfunction "3_3") (pintype "passive"))
      (node (ref "XFMR1") (pin "3") (pinfunction "3_3") (pintype "passive"))
    )
    (net (code "58") (name "Net-(U1-A0)") (class "Default")
      (node (ref "J_A0") (pin "3") (pintype "passive"))
      (node (ref "U1") (pin "45") (pinfunction "A0_45") (pintype "input"))
    )
    (net (code "59") (name "Net-(U1-A1)") (class "Default")
      (node (ref "J_A1") (pin "3") (pintype "passive"))
      (node (ref "U1") (pin "46") (pinfunction "A1_46") (pintype "input"))
    )
    (net (code "60") (name "Net-(U1-A2)") (class "Default")
      (node (ref "J_A2") (pin "3") (pintype "passive"))
      (node (ref "U1") (pin "47") (pinfunction "A2_47") (pintype "input"))
    )
    (net (code "61") (name "Net-(U1-A3)") (class "Default")
      (node (ref "J_A3") (pin "3") (pintype "passive"))
      (node (ref "U1") (pin "48") (pinfunction "A3_48") (pintype "input"))
    )
    (net (code "62") (name "Net-(U1-CSB_(IMA))") (class "Default")
      (node (ref "J_IMA") (pin "3") (pintype "passive"))
      (node (ref "U1") (pin "41") (pinfunction "CSB_(IMA)_41") (pintype "bidirectional"))
    )
    (net (code "63") (name "Net-(U1-ISOMD)") (class "Default")
      (node (ref "J_ISOMD") (pin "3") (pintype "passive"))
      (node (ref "U1") (pin "40") (pinfunction "ISOMD_40") (pintype "input"))
    )
    (net (code "64") (name "Net-(U1-S1)") (class "Default")
      (node (ref "TPS1") (pin "1") (pinfunction "1_1") (pintype "passive"))
      (node (ref "U1") (pin "25") (pinfunction "S1_25") (pintype "bidirectional"))
    )
    (net (code "65") (name "Net-(U1-S2)") (class "Default")
      (node (ref "TPS2") (pin "1") (pinfunction "1_1") (pintype "passive"))
      (node (ref "U1") (pin "23") (pinfunction "S2_23") (pintype "bidirectional"))
    )
    (net (code "66") (name "Net-(U1-S3)") (class "Default")
      (node (ref "TPS3") (pin "1") (pinfunction "1_1") (pintype "passive"))
      (node (ref "U1") (pin "21") (pinfunction "S3_21") (pintype "bidirectional"))
    )
    (net (code "67") (name "Net-(U1-S4)") (class "Default")
      (node (ref "TPS4") (pin "1") (pinfunction "1_1") (pintype "passive"))
      (node (ref "U1") (pin "19") (pinfunction "S4_19") (pintype "bidirectional"))
    )
    (net (code "68") (name "Net-(U1-S7)") (class "Default")
      (node (ref "TPS5") (pin "1") (pinfunction "1_1") (pintype "passive"))
      (node (ref "U1") (pin "13") (pinfunction "S7_13") (pintype "bidirectional"))
    )
    (net (code "69") (name "Net-(U1-S8)") (class "Default")
      (node (ref "TPS6") (pin "1") (pinfunction "1_1") (pintype "passive"))
      (node (ref "U1") (pin "11") (pinfunction "S8_11") (pintype "bidirectional"))
    )
    (net (code "70") (name "Net-(U1-S9)") (class "Default")
      (node (ref "TPS7") (pin "1") (pinfunction "1_1") (pintype "passive"))
      (node (ref "U1") (pin "9") (pinfunction "S9_9") (pintype "bidirectional"))
    )
    (net (code "71") (name "Net-(U1-S10)") (class "Default")
      (node (ref "TPS8") (pin "1") (pinfunction "1_1") (pintype "passive"))
      (node (ref "U1") (pin "7") (pinfunction "S10_7") (pintype "bidirectional"))
    )
    (net (code "72") (name "Net-(U1-SCK_(IPA))") (class "Default")
      (node (ref "J_IPA") (pin "3") (pintype "passive"))
      (node (ref "U1") (pin "42") (pinfunction "SCK_(IPA)_42") (pintype "bidirectional"))
    )
    (net (code "73") (name "Net-(U1-SDI_(ICMP))") (class "Default")
      (node (ref "J_ICMP") (pin "3") (pintype "passive"))
      (node (ref "U1") (pin "43") (pinfunction "SDI_(ICMP)_43") (pintype "input"))
    )
    (net (code "74") (name "Net-(U1-SDO_(IBIAS))") (class "Default")
      (node (ref "J_IBIAS") (pin "3") (pintype "passive"))
      (node (ref "U1") (pin "44") (pinfunction "SDO_(IBIAS)_44") (pintype "bidirectional"))
    )
    (net (code "75") (name "Net-(U1-SWTEN)") (class "Default")
      (node (ref "J_DTEN") (pin "3") (pintype "passive"))
      (node (ref "U1") (pin "36") (pinfunction "SWTEN_36") (pintype "input"))
    )
    (net (code "76") (name "Net-(U1-WDT)") (class "Default")
      (node (ref "TP_WDT") (pin "1") (pinfunction "1_1") (pintype "passive"))
      (node (ref "U1") (pin "39") (pinfunction "WDT_39") (pintype "tri_state"))
    )
    (net (code "77") (name "unconnected-(U1-S5-Pad17)") (class "Default")
      (node (ref "U1") (pin "17") (pinfunction "S5_17") (pintype "bidirectional"))
    )
    (net (code "78") (name "unconnected-(U1-S6-Pad15)") (class "Default")
      (node (ref "U1") (pin "15") (pinfunction "S6_15") (pintype "bidirectional"))
    )
    (net (code "79") (name "unconnected-(U1-S11-Pad5)") (class "Default")
      (node (ref "U1") (pin "5") (pinfunction "S11_5") (pintype "bidirectional"))
    )
    (net (code "80") (name "unconnected-(U1-S12-Pad3)") (class "Default")
      (node (ref "U1") (pin "3") (pinfunction "S12_3") (pintype "bidirectional"))
    )
    (net (code "81") (name "unconnected-(XFMR2-Pad1)") (class "Default")
      (node (ref "XFMR2") (pin "1") (pinfunction "1_1") (pintype "passive"))
    )
    (net (code "82") (name "unconnected-(XFMR2-Pad2)") (class "Default")
      (node (ref "XFMR2") (pin "2") (pinfunction "2_2") (pintype "passive"))
    )
    (net (code "83") (name "unconnected-(XFMR2-Pad3)") (class "Default")
      (node (ref "XFMR2") (pin "3") (pinfunction "3_3") (pintype "passive"))
    )
    (net (code "84") (name "unconnected-(XFMR2-Pad5)") (class "Default")
      (node (ref "XFMR2") (pin "5") (pinfunction "5_5") (pintype "passive"))
    )
    (net (code "85") (name "unconnected-(XFMR2-Pad10)") (class "Default")
      (node (ref "XFMR2") (pin "10") (pinfunction "10_10") (pintype "passive"))
    )
    (net (code "86") (name "unconnected-(XFMR2-Pad11)") (class "Default")
      (node (ref "XFMR2") (pin "11") (pinfunction "11_11") (pintype "passive"))
    )
    (net (code "87") (name "unconnected-(XFMR2-Pad12)") (class "Default")
      (node (ref "XFMR2") (pin "12") (pinfunction "12_12") (pintype "passive"))
    )
  )
)
